# SAML21_Xplained_Pro_current_measurement.net
KiCad netlist of a schematic drawn in Altium Designer
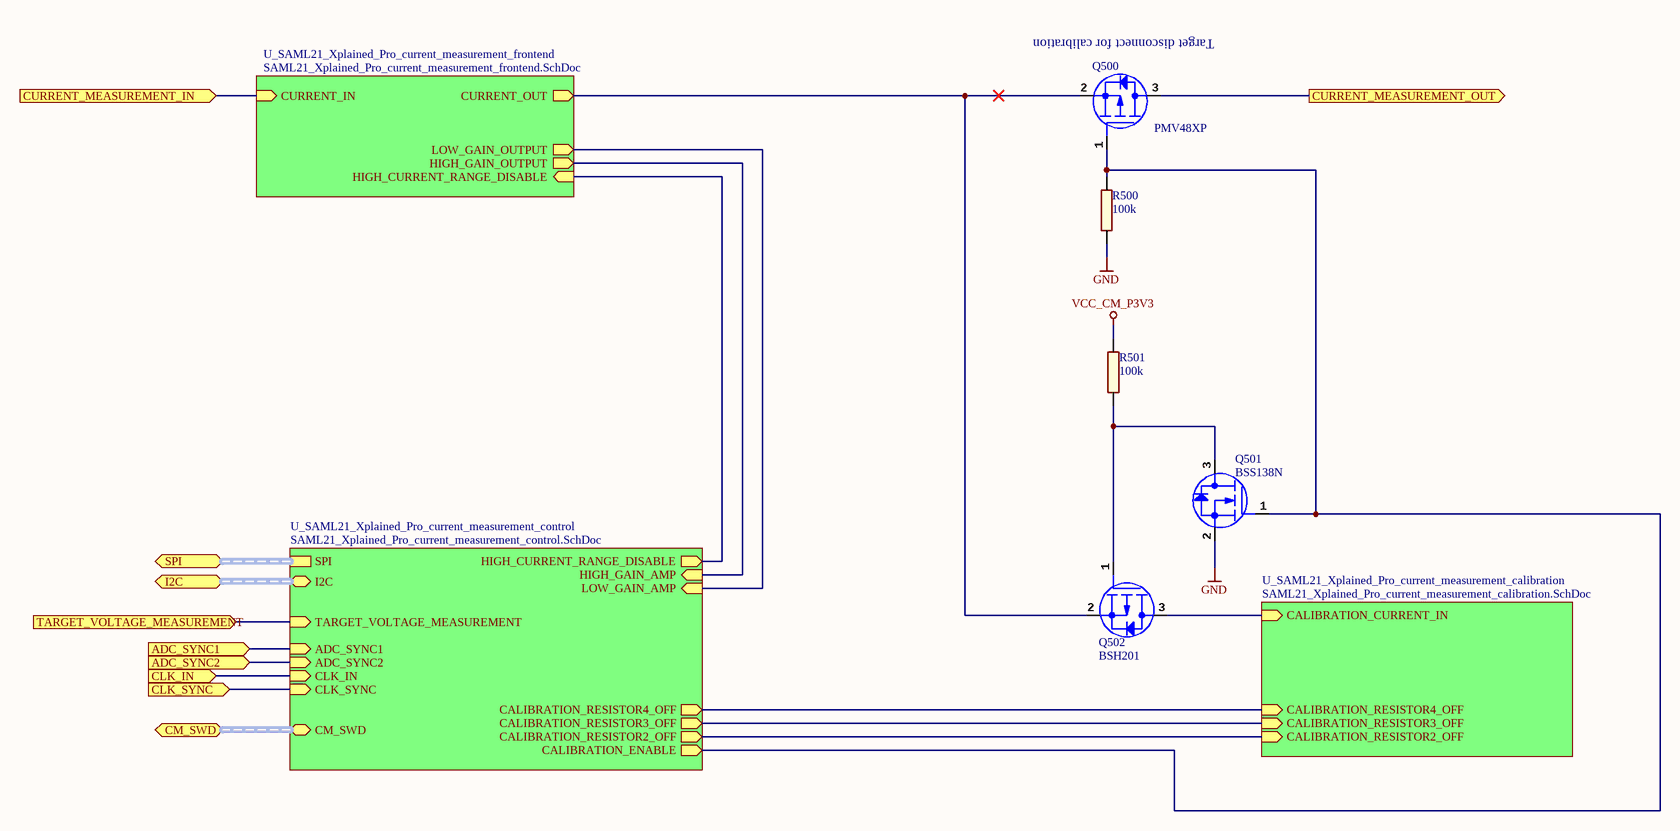
[diagram p0: SAML21_Xplained_Pro_current_measurement.SchDoc]

(export (version "E")
  (design (tool "Eeschema 10.0.6"))
  (components
    (comp (ref "Q500")
      (value "PMV48XP")
      (footprint "AP5-00002")
      (fields
        (field (name "MANUFACTURER") "NXP")
        (field (name "MPN") "PMV48XP,215")
        (field (name "Comment") "MOSFET_P_GSD")
      )
      (libsource (lib "AltiumDbLib") (part "MOSFET_P_GSD"))
    )
    (comp (ref "Q501")
      (value "BSS138N")
      (footprint "AP5-00002")
      (fields (field (name "MANUFACTURER") "Infineon") (field (name "Comment") "MOSFET_N_GSD"))
      (libsource (lib "AltiumDbLib") (part "MOSFET_N_GSD"))
    )
    (comp (ref "Q502")
      (value "BSH201")
      (footprint "AP5-00002")
      (fields
        (field (name "MANUFACTURER") "NXP")
        (field (name "MPN") "BSH201,215")
        (field (name "Comment") "MOSFET_P_GSD")
      )
      (libsource (lib "AltiumDbLib") (part "MOSFET_P_GSD"))
    )
    (comp (ref "R500")
      (value "100k")
      (footprint "AP2-00011")
      (description "Thick film resistor, SMD 0402, 1/16W, 1%")
      (fields (field (name "TOLERANCE") "1 %") (field (name "Comment") "R2"))
      (libsource (lib "AltiumDbLib") (part "R2"))
    )
    (comp (ref "R501")
      (value "100k")
      (footprint "AP2-00011")
      (description "Thick film resistor, SMD 0402, 1/16W, 1%")
      (fields (field (name "TOLERANCE") "1 %") (field (name "Comment") "R2"))
      (libsource (lib "") (part "R2_1"))
    )
  )
  (nets
    (net (code "6") (name "/CALIBRATION_CURRENT_IN") (class "Default")
      (node (ref "Q502") (pin "3") (pinfunction "D_3") (pintype "passive"))
    )
    (net (code "7") (name "/CALIBRATION_ENABLE") (class "Default")
      (node (ref "Q500") (pin "1") (pinfunction "G_1") (pintype "passive"))
      (node (ref "Q501") (pin "1") (pinfunction "G_1") (pintype "passive"))
      (node (ref "R500") (pin "2") (pinfunction "2_2") (pintype "passive"))
    )
    (net (code "15") (name "/CURRENT_MEASUREMENT_OUT") (class "Default")
      (node (ref "Q500") (pin "3") (pinfunction "D_3") (pintype "passive"))
    )
    (net (code "16") (name "/CURRENT_OUT") (class "Default")
      (node (ref "Q500") (pin "2") (pinfunction "S_2") (pintype "passive"))
      (node (ref "Q502") (pin "2") (pinfunction "S_2") (pintype "passive"))
    )
    (net (code "23") (name "GND") (class "Default")
      (node (ref "Q501") (pin "2") (pinfunction "S_2") (pintype "passive"))
      (node (ref "R500") (pin "1") (pinfunction "1_1") (pintype "passive"))
    )
    (net (code "24") (name "Net-(Q501-D)") (class "Default")
      (node (ref "Q501") (pin "3") (pinfunction "D_3") (pintype "passive"))
      (node (ref "Q502") (pin "1") (pinfunction "G_1") (pintype "passive"))
      (node (ref "R501") (pin "1") (pinfunction "1_1") (pintype "passive"))
    )
    (net (code "25") (name "VCC_CM_P3V3") (class "Default")
      (node (ref "R501") (pin "2") (pinfunction "2_2") (pintype "passive"))
    )
  )
)
